# BMBurner_V1_1.net
KiCad netlist of a schematic drawn in EAGLE
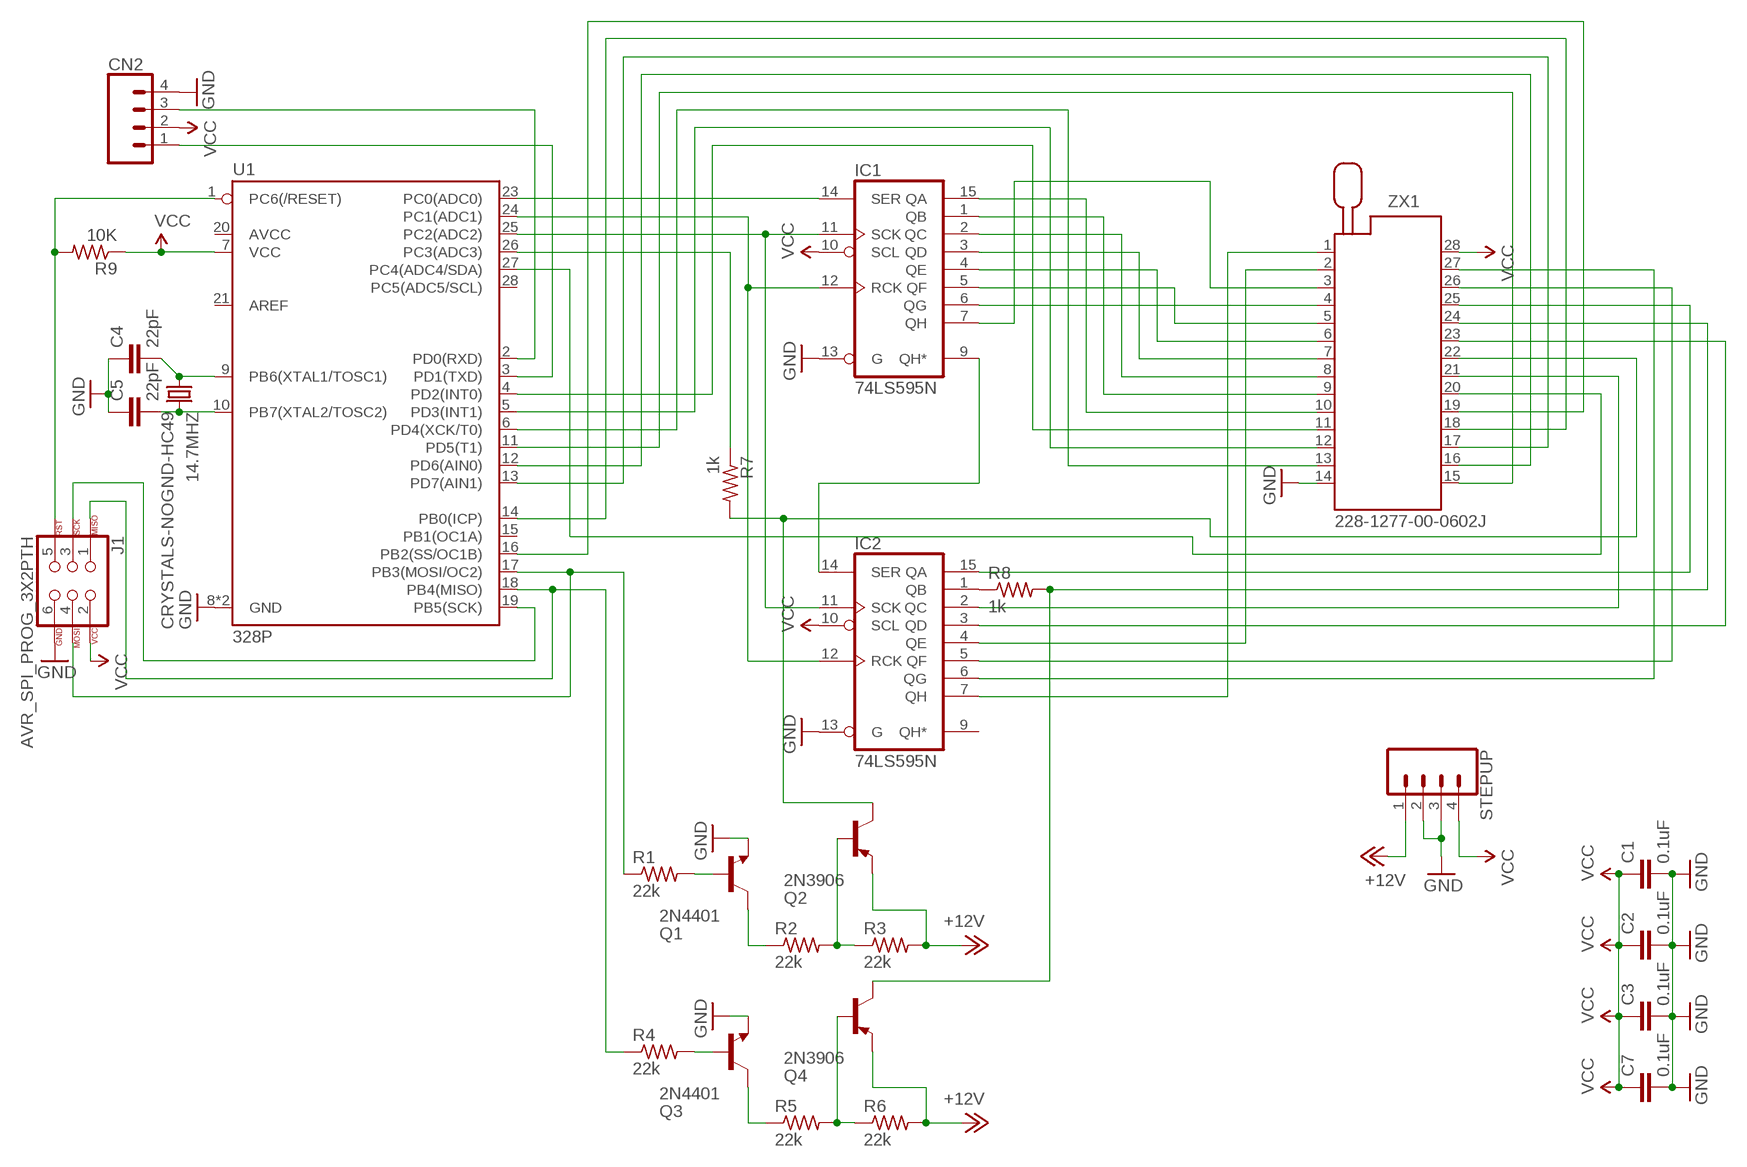
[diagram p0: schematic, sheet 1]

(export (version "E")
  (design (tool "Eeschema 10.0.6"))
  (components
    (comp (ref "14.7MHZ")
      (value "CRYSTALS-NOGND-HC49")
      (footprint "eagle-import:HC49")
      (libsource (lib "eagle-import") (part "CRYSTALS-NOGND-HC49"))
    )
    (comp (ref "C1")
      (value "0.1uF")
      (footprint "eagle-import:CAP-PTH-SMALL")
      (libsource (lib "eagle-import") (part "CAPPTH"))
    )
    (comp (ref "C2")
      (value "0.1uF")
      (footprint "eagle-import:CAP-PTH-SMALL")
      (libsource (lib "eagle-import") (part "CAPPTH"))
    )
    (comp (ref "C3")
      (value "0.1uF")
      (footprint "eagle-import:CAP-PTH-SMALL")
      (libsource (lib "eagle-import") (part "CAPPTH"))
    )
    (comp (ref "C4")
      (value "22pF")
      (footprint "eagle-import:CAP-PTH-SMALL")
      (libsource (lib "eagle-import") (part "CAPPTH"))
    )
    (comp (ref "C5")
      (value "22pF")
      (footprint "eagle-import:CAP-PTH-SMALL")
      (libsource (lib "eagle-import") (part "CAPPTH"))
    )
    (comp (ref "C7")
      (value "0.1uF")
      (footprint "eagle-import:CAP-PTH-SMALL")
      (libsource (lib "eagle-import") (part "CAPPTH"))
    )
    (comp (ref "CN2")
      (value "CONN_04")
      (footprint "eagle-import:1X04")
      (libsource (lib "eagle-import") (part "CONN_04"))
    )
    (comp (ref "IC1")
      (value "74LS595N")
      (footprint "eagle-import:DIL16")
      (fields (field (name "SPICEPREFIX") "X"))
      (libsource (lib "eagle-import") (part "74595NLS"))
    )
    (comp (ref "IC2")
      (value "74LS595N")
      (footprint "eagle-import:DIL16")
      (fields (field (name "SPICEPREFIX") "X"))
      (libsource (lib "eagle-import") (part "74595NLS"))
    )
    (comp (ref "J1")
      (value "AVR_SPI_PROG_3X2PTH")
      (footprint "eagle-import:2X3")
      (libsource (lib "eagle-import") (part "AVR_SPI_PROG_3X2PTH"))
    )
    (comp (ref "Q1")
      (value "2N4401")
      (footprint "eagle-import:TO92-EBC")
      (libsource (lib "eagle-import") (part "BC447"))
    )
    (comp (ref "Q2")
      (value "2N3906")
      (footprint "eagle-import:TO92-EBC")
      (libsource (lib "eagle-import") (part "BC448"))
    )
    (comp (ref "Q3")
      (value "2N4401")
      (footprint "eagle-import:TO92-EBC")
      (libsource (lib "eagle-import") (part "BC447"))
    )
    (comp (ref "Q4")
      (value "2N3906")
      (footprint "eagle-import:TO92-EBC")
      (libsource (lib "eagle-import") (part "BC448"))
    )
    (comp (ref "R1")
      (value "22k")
      (footprint "eagle-import:0204_5")
      (fields (field (name "SPICEPREFIX") "R"))
      (libsource (lib "eagle-import") (part "R-US_0204/5"))
    )
    (comp (ref "R2")
      (value "22k")
      (footprint "eagle-import:0204_5")
      (libsource (lib "eagle-import") (part "R-US_0204/5"))
    )
    (comp (ref "R3")
      (value "22k")
      (footprint "eagle-import:0204_5")
      (libsource (lib "eagle-import") (part "R-US_0204/5"))
    )
    (comp (ref "R4")
      (value "22k")
      (footprint "eagle-import:0204_5")
      (libsource (lib "eagle-import") (part "R-US_0204/5"))
    )
    (comp (ref "R5")
      (value "22k")
      (footprint "eagle-import:0204_5")
      (libsource (lib "eagle-import") (part "R-US_0204/5"))
    )
    (comp (ref "R6")
      (value "22k")
      (footprint "eagle-import:0204_5")
      (libsource (lib "eagle-import") (part "R-US_0204/5"))
    )
    (comp (ref "R7")
      (value "1k")
      (footprint "eagle-import:0204_5")
      (libsource (lib "eagle-import") (part "R-US_0204/5"))
    )
    (comp (ref "R8")
      (value "1k")
      (footprint "eagle-import:0204_5")
      (libsource (lib "eagle-import") (part "R-US_0204/5"))
    )
    (comp (ref "R9")
      (value "10K")
      (footprint "eagle-import:0204_5")
      (libsource (lib "eagle-import") (part "R-US_0204/5"))
    )
    (comp (ref "STEPUP")
      (value "CONN_04")
      (footprint "eagle-import:1X04")
      (libsource (lib "eagle-import") (part "CONN_04"))
    )
    (comp (ref "U1")
      (value "328P")
      (footprint "eagle-import:DIP28")
      (libsource (lib "eagle-import") (part "ATMEGA328P_PDIP"))
    )
    (comp (ref "ZX1")
      (value "228-1277-00-0602J")
      (footprint "eagle-import:228-1277-00-0602J")
      (fields (field (name "MF") "3M"))
      (libsource (lib "eagle-import") (part "228-?00-0602J1277-"))
    )
  )
  (nets
    (net (code "1") (name "+12V") (class "Default")
      (node (ref "Q2") (pin "E") (pinfunction "E_E") (pintype "passive"))
      (node (ref "Q4") (pin "E") (pinfunction "E_E") (pintype "passive"))
      (node (ref "R3") (pin "2") (pinfunction "2_2") (pintype "passive"))
      (node (ref "R6") (pin "2") (pinfunction "2_2") (pintype "passive"))
      (node (ref "STEPUP") (pin "1") (pinfunction "1_1") (pintype "passive"))
    )
    (net (code "2") (name "GND") (class "Default")
      (node (ref "C1") (pin "2") (pinfunction "2_2") (pintype "passive"))
      (node (ref "C2") (pin "2") (pinfunction "2_2") (pintype "passive"))
      (node (ref "C3") (pin "2") (pinfunction "2_2") (pintype "passive"))
      (node (ref "C4") (pin "1") (pinfunction "1_1") (pintype "passive"))
      (node (ref "C5") (pin "1") (pinfunction "1_1") (pintype "passive"))
      (node (ref "C7") (pin "2") (pinfunction "2_2") (pintype "passive"))
      (node (ref "CN2") (pin "4") (pinfunction "4_4") (pintype "passive"))
      (node (ref "IC1") (pin "13") (pinfunction "G_13") (pintype "input"))
      (node (ref "IC2") (pin "13") (pinfunction "G_13") (pintype "input"))
      (node (ref "J1") (pin "6") (pinfunction "6_6") (pintype "passive"))
      (node (ref "Q1") (pin "E") (pinfunction "E_E") (pintype "passive"))
      (node (ref "Q3") (pin "E") (pinfunction "E_E") (pintype "passive"))
      (node (ref "STEPUP") (pin "2") (pinfunction "2_2") (pintype "passive"))
      (node (ref "STEPUP") (pin "3") (pinfunction "3_3") (pintype "passive"))
      (node (ref "U1") (pin "22") (pinfunction "GND_22") (pintype "bidirectional"))
      (node (ref "U1") (pin "8") (pinfunction "GND_8") (pintype "bidirectional"))
      (node (ref "ZX1") (pin "14") (pinfunction "14_14") (pintype "passive"))
    )
    (net (code "3") (name "Net-(IC1A-QA)") (class "Default")
      (node (ref "IC1") (pin "15") (pinfunction "QA_15") (pintype "tri_state"))
      (node (ref "ZX1") (pin "10") (pinfunction "10_10") (pintype "passive"))
    )
    (net (code "4") (name "Net-(IC1A-QB)") (class "Default")
      (node (ref "IC1") (pin "1") (pinfunction "QB_1") (pintype "tri_state"))
      (node (ref "ZX1") (pin "9") (pinfunction "9_9") (pintype "passive"))
    )
    (net (code "5") (name "Net-(IC1A-QC)") (class "Default")
      (node (ref "IC1") (pin "2") (pinfunction "QC_2") (pintype "tri_state"))
      (node (ref "ZX1") (pin "8") (pinfunction "8_8") (pintype "passive"))
    )
    (net (code "6") (name "Net-(IC1A-QD)") (class "Default")
      (node (ref "IC1") (pin "3") (pinfunction "QD_3") (pintype "tri_state"))
      (node (ref "ZX1") (pin "7") (pinfunction "7_7") (pintype "passive"))
    )
    (net (code "7") (name "Net-(IC1A-QE)") (class "Default")
      (node (ref "IC1") (pin "4") (pinfunction "QE_4") (pintype "tri_state"))
      (node (ref "ZX1") (pin "6") (pinfunction "6_6") (pintype "passive"))
    )
    (net (code "8") (name "Net-(IC1A-QF)") (class "Default")
      (node (ref "IC1") (pin "5") (pinfunction "QF_5") (pintype "tri_state"))
      (node (ref "ZX1") (pin "5") (pinfunction "5_5") (pintype "passive"))
    )
    (net (code "9") (name "Net-(IC1A-QG)") (class "Default")
      (node (ref "IC1") (pin "6") (pinfunction "QG_6") (pintype "tri_state"))
      (node (ref "ZX1") (pin "4") (pinfunction "4_4") (pintype "passive"))
    )
    (net (code "10") (name "Net-(IC1A-QH)") (class "Default")
      (node (ref "IC1") (pin "7") (pinfunction "QH_7") (pintype "tri_state"))
      (node (ref "ZX1") (pin "3") (pinfunction "3_3") (pintype "passive"))
    )
    (net (code "11") (name "Net-(IC1A-QH*)") (class "Default")
      (node (ref "IC1") (pin "9") (pinfunction "QH*_9") (pintype "tri_state"))
      (node (ref "IC2") (pin "14") (pinfunction "SER_14") (pintype "input"))
    )
    (net (code "12") (name "Net-(IC1A-RCK)") (class "Default")
      (node (ref "IC1") (pin "12") (pinfunction "RCK_12") (pintype "input"))
      (node (ref "IC2") (pin "12") (pinfunction "RCK_12") (pintype "input"))
      (node (ref "U1") (pin "24") (pinfunction "PC1(ADC1)_24") (pintype "bidirectional"))
    )
    (net (code "13") (name "Net-(IC1A-SCK)") (class "Default")
      (node (ref "IC1") (pin "11") (pinfunction "SCK_11") (pintype "input"))
      (node (ref "IC2") (pin "11") (pinfunction "SCK_11") (pintype "input"))
      (node (ref "U1") (pin "25") (pinfunction "PC2(ADC2)_25") (pintype "bidirectional"))
    )
    (net (code "14") (name "Net-(IC1A-SER)") (class "Default")
      (node (ref "IC1") (pin "14") (pinfunction "SER_14") (pintype "input"))
      (node (ref "U1") (pin "23") (pinfunction "PC0(ADC0)_23") (pintype "bidirectional"))
    )
    (net (code "15") (name "Net-(IC2A-QA)") (class "Default")
      (node (ref "IC2") (pin "15") (pinfunction "QA_15") (pintype "tri_state"))
      (node (ref "ZX1") (pin "25") (pinfunction "25_25") (pintype "passive"))
    )
    (net (code "16") (name "Net-(IC2A-QB)") (class "Default")
      (node (ref "IC2") (pin "1") (pinfunction "QB_1") (pintype "tri_state"))
      (node (ref "R8") (pin "1") (pinfunction "1_1") (pintype "passive"))
    )
    (net (code "17") (name "Net-(IC2A-QC)") (class "Default")
      (node (ref "IC2") (pin "2") (pinfunction "QC_2") (pintype "tri_state"))
      (node (ref "ZX1") (pin "21") (pinfunction "21_21") (pintype "passive"))
    )
    (net (code "18") (name "Net-(IC2A-QD)") (class "Default")
      (node (ref "IC2") (pin "3") (pinfunction "QD_3") (pintype "tri_state"))
      (node (ref "ZX1") (pin "23") (pinfunction "23_23") (pintype "passive"))
    )
    (net (code "19") (name "Net-(IC2A-QE)") (class "Default")
      (node (ref "IC2") (pin "4") (pinfunction "QE_4") (pintype "tri_state"))
      (node (ref "ZX1") (pin "2") (pinfunction "2_2") (pintype "passive"))
    )
    (net (code "20") (name "Net-(IC2A-QF)") (class "Default")
      (node (ref "IC2") (pin "5") (pinfunction "QF_5") (pintype "tri_state"))
      (node (ref "ZX1") (pin "26") (pinfunction "26_26") (pintype "passive"))
    )
    (net (code "21") (name "Net-(IC2A-QG)") (class "Default")
      (node (ref "IC2") (pin "6") (pinfunction "QG_6") (pintype "tri_state"))
      (node (ref "ZX1") (pin "27") (pinfunction "27_27") (pintype "passive"))
    )
    (net (code "22") (name "Net-(IC2A-QH)") (class "Default")
      (node (ref "IC2") (pin "7") (pinfunction "QH_7") (pintype "tri_state"))
      (node (ref "ZX1") (pin "1") (pinfunction "1_1") (pintype "passive"))
    )
    (net (code "23") (name "Net-(Q1-PadB)") (class "Default")
      (node (ref "Q1") (pin "B") (pinfunction "B_B") (pintype "passive"))
      (node (ref "R1") (pin "2") (pinfunction "2_2") (pintype "passive"))
    )
    (net (code "24") (name "Net-(Q1-PadC)") (class "Default")
      (node (ref "Q1") (pin "C") (pinfunction "C_C") (pintype "passive"))
      (node (ref "R2") (pin "1") (pinfunction "1_1") (pintype "passive"))
    )
    (net (code "25") (name "Net-(Q2-PadB)") (class "Default")
      (node (ref "Q2") (pin "B") (pinfunction "B_B") (pintype "passive"))
      (node (ref "R2") (pin "2") (pinfunction "2_2") (pintype "passive"))
      (node (ref "R3") (pin "1") (pinfunction "1_1") (pintype "passive"))
    )
    (net (code "26") (name "Net-(Q2-PadC)") (class "Default")
      (node (ref "Q2") (pin "C") (pinfunction "C_C") (pintype "passive"))
      (node (ref "R7") (pin "2") (pinfunction "2_2") (pintype "passive"))
      (node (ref "ZX1") (pin "22") (pinfunction "22_22") (pintype "passive"))
    )
    (net (code "27") (name "Net-(Q3-PadB)") (class "Default")
      (node (ref "Q3") (pin "B") (pinfunction "B_B") (pintype "passive"))
      (node (ref "R4") (pin "2") (pinfunction "2_2") (pintype "passive"))
    )
    (net (code "28") (name "Net-(Q3-PadC)") (class "Default")
      (node (ref "Q3") (pin "C") (pinfunction "C_C") (pintype "passive"))
      (node (ref "R5") (pin "1") (pinfunction "1_1") (pintype "passive"))
    )
    (net (code "29") (name "Net-(Q4-PadB)") (class "Default")
      (node (ref "Q4") (pin "B") (pinfunction "B_B") (pintype "passive"))
      (node (ref "R5") (pin "2") (pinfunction "2_2") (pintype "passive"))
      (node (ref "R6") (pin "1") (pinfunction "1_1") (pintype "passive"))
    )
    (net (code "30") (name "Net-(Q4-PadC)") (class "Default")
      (node (ref "Q4") (pin "C") (pinfunction "C_C") (pintype "passive"))
      (node (ref "R8") (pin "2") (pinfunction "2_2") (pintype "passive"))
      (node (ref "ZX1") (pin "24") (pinfunction "24_24") (pintype "passive"))
    )
    (net (code "31") (name "Net-(U1-PB0(ICP))") (class "Default")
      (node (ref "U1") (pin "14") (pinfunction "PB0(ICP)_14") (pintype "bidirectional"))
      (node (ref "ZX1") (pin "18") (pinfunction "18_18") (pintype "passive"))
    )
    (net (code "32") (name "Net-(U1-PB2(SS{slash}OC1B))") (class "Default")
      (node (ref "U1") (pin "16") (pinfunction "PB2(SS/OC1B)_16") (pintype "bidirectional"))
      (node (ref "ZX1") (pin "19") (pinfunction "19_19") (pintype "passive"))
    )
    (net (code "33") (name "Net-(U1-PB3(MOSI{slash}OC2))") (class "Default")
      (node (ref "J1") (pin "4") (pinfunction "4_4") (pintype "passive"))
      (node (ref "R1") (pin "1") (pinfunction "1_1") (pintype "passive"))
      (node (ref "U1") (pin "17") (pinfunction "PB3(MOSI/OC2)_17") (pintype "bidirectional"))
    )
    (net (code "34") (name "Net-(U1-PB4(MISO))") (class "Default")
      (node (ref "J1") (pin "1") (pinfunction "1_1") (pintype "passive"))
      (node (ref "R4") (pin "1") (pinfunction "1_1") (pintype "passive"))
      (node (ref "U1") (pin "18") (pinfunction "PB4(MISO)_18") (pintype "bidirectional"))
    )
    (net (code "35") (name "Net-(U1-PB5(SCK))") (class "Default")
      (node (ref "J1") (pin "3") (pinfunction "3_3") (pintype "passive"))
      (node (ref "U1") (pin "19") (pinfunction "PB5(SCK)_19") (pintype "bidirectional"))
    )
    (net (code "36") (name "Net-(U1-PB6(XTAL1{slash}TOSC1))") (class "Default")
      (node (ref "14.7MHZ") (pin "1") (pinfunction "1_1") (pintype "passive"))
      (node (ref "C4") (pin "2") (pinfunction "2_2") (pintype "passive"))
      (node (ref "U1") (pin "9") (pinfunction "PB6(XTAL1/TOSC1)_9") (pintype "bidirectional"))
    )
    (net (code "37") (name "Net-(U1-PB7(XTAL2{slash}TOSC2))") (class "Default")
      (node (ref "14.7MHZ") (pin "2") (pinfunction "2_2") (pintype "passive"))
      (node (ref "C5") (pin "2") (pinfunction "2_2") (pintype "passive"))
      (node (ref "U1") (pin "10") (pinfunction "PB7(XTAL2/TOSC2)_10") (pintype "bidirectional"))
    )
    (net (code "38") (name "Net-(U1-PC3(ADC3))") (class "Default")
      (node (ref "R7") (pin "1") (pinfunction "1_1") (pintype "passive"))
      (node (ref "U1") (pin "26") (pinfunction "PC3(ADC3)_26") (pintype "bidirectional"))
    )
    (net (code "39") (name "Net-(U1-PC4(ADC4{slash}SDA))") (class "Default")
      (node (ref "U1") (pin "27") (pinfunction "PC4(ADC4/SDA)_27") (pintype "bidirectional"))
      (node (ref "ZX1") (pin "20") (pinfunction "20_20") (pintype "passive"))
    )
    (net (code "40") (name "Net-(U1-PC6({slash}RESET))") (class "Default")
      (node (ref "J1") (pin "5") (pinfunction "5_5") (pintype "passive"))
      (node (ref "R9") (pin "2") (pinfunction "2_2") (pintype "passive"))
      (node (ref "U1") (pin "1") (pinfunction "PC6(/RESET)_1") (pintype "bidirectional"))
    )
    (net (code "41") (name "Net-(U1-PD0(RXD))") (class "Default")
      (node (ref "CN2") (pin "3") (pinfunction "3_3") (pintype "passive"))
      (node (ref "U1") (pin "2") (pinfunction "PD0(RXD)_2") (pintype "bidirectional"))
    )
    (net (code "42") (name "Net-(U1-PD1(TXD))") (class "Default")
      (node (ref "CN2") (pin "1") (pinfunction "1_1") (pintype "passive"))
      (node (ref "U1") (pin "3") (pinfunction "PD1(TXD)_3") (pintype "bidirectional"))
    )
    (net (code "43") (name "Net-(U1-PD2(INT0))") (class "Default")
      (node (ref "U1") (pin "4") (pinfunction "PD2(INT0)_4") (pintype "bidirectional"))
      (node (ref "ZX1") (pin "11") (pinfunction "11_11") (pintype "passive"))
    )
    (net (code "44") (name "Net-(U1-PD3(INT1))") (class "Default")
      (node (ref "U1") (pin "5") (pinfunction "PD3(INT1)_5") (pintype "bidirectional"))
      (node (ref "ZX1") (pin "12") (pinfunction "12_12") (pintype "passive"))
    )
    (net (code "45") (name "Net-(U1-PD4(XCK{slash}T0))") (class "Default")
      (node (ref "U1") (pin "6") (pinfunction "PD4(XCK/T0)_6") (pintype "bidirectional"))
      (node (ref "ZX1") (pin "13") (pinfunction "13_13") (pintype "passive"))
    )
    (net (code "46") (name "Net-(U1-PD5(T1))") (class "Default")
      (node (ref "U1") (pin "11") (pinfunction "PD5(T1)_11") (pintype "bidirectional"))
      (node (ref "ZX1") (pin "15") (pinfunction "15_15") (pintype "passive"))
    )
    (net (code "47") (name "Net-(U1-PD6(AIN0))") (class "Default")
      (node (ref "U1") (pin "12") (pinfunction "PD6(AIN0)_12") (pintype "bidirectional"))
      (node (ref "ZX1") (pin "16") (pinfunction "16_16") (pintype "passive"))
    )
    (net (code "48") (name "Net-(U1-PD7(AIN1))") (class "Default")
      (node (ref "U1") (pin "13") (pinfunction "PD7(AIN1)_13") (pintype "bidirectional"))
      (node (ref "ZX1") (pin "17") (pinfunction "17_17") (pintype "passive"))
    )
    (net (code "49") (name "VCC") (class "Default")
      (node (ref "C1") (pin "1") (pinfunction "1_1") (pintype "passive"))
      (node (ref "C2") (pin "1") (pinfunction "1_1") (pintype "passive"))
      (node (ref "C3") (pin "1") (pinfunction "1_1") (pintype "passive"))
      (node (ref "C7") (pin "1") (pinfunction "1_1") (pintype "passive"))
      (node (ref "CN2") (pin "2") (pinfunction "2_2") (pintype "passive"))
      (node (ref "IC1") (pin "10") (pinfunction "SCL_10") (pintype "input"))
      (node (ref "IC2") (pin "10") (pinfunction "SCL_10") (pintype "input"))
      (node (ref "J1") (pin "2") (pinfunction "2_2") (pintype "passive"))
      (node (ref "R9") (pin "1") (pinfunction "1_1") (pintype "passive"))
      (node (ref "STEPUP") (pin "4") (pinfunction "4_4") (pintype "passive"))
      (node (ref "U1") (pin "7") (pinfunction "VCC_7") (pintype "bidirectional"))
      (node (ref "ZX1") (pin "28") (pinfunction "28_28") (pintype "passive"))
    )
    (net (code "50") (name "unconnected-(IC2A-QH*-Pad9)") (class "Default")
      (node (ref "IC2") (pin "9") (pinfunction "QH*_9") (pintype "tri_state"))
    )
    (net (code "51") (name "unconnected-(U1-AREF-Pad21)") (class "Default")
      (node (ref "U1") (pin "21") (pinfunction "AREF_21") (pintype "bidirectional"))
    )
    (net (code "52") (name "unconnected-(U1-AVCC-Pad20)") (class "Default")
      (node (ref "U1") (pin "20") (pinfunction "AVCC_20") (pintype "bidirectional"))
    )
    (net (code "53") (name "unconnected-(U1-PB1(OC1A)-Pad15)") (class "Default")
      (node (ref "U1") (pin "15") (pinfunction "PB1(OC1A)_15") (pintype "bidirectional"))
    )
    (net (code "54") (name "unconnected-(U1-PC5(ADC5{slash}SCL)-Pad28)") (class "Default")
      (node (ref "U1") (pin "28") (pinfunction "PC5(ADC5/SCL)_28") (pintype "bidirectional"))
    )
  )
)
